# scld_winslow.net
KiCad netlist of a schematic drawn in EAGLE
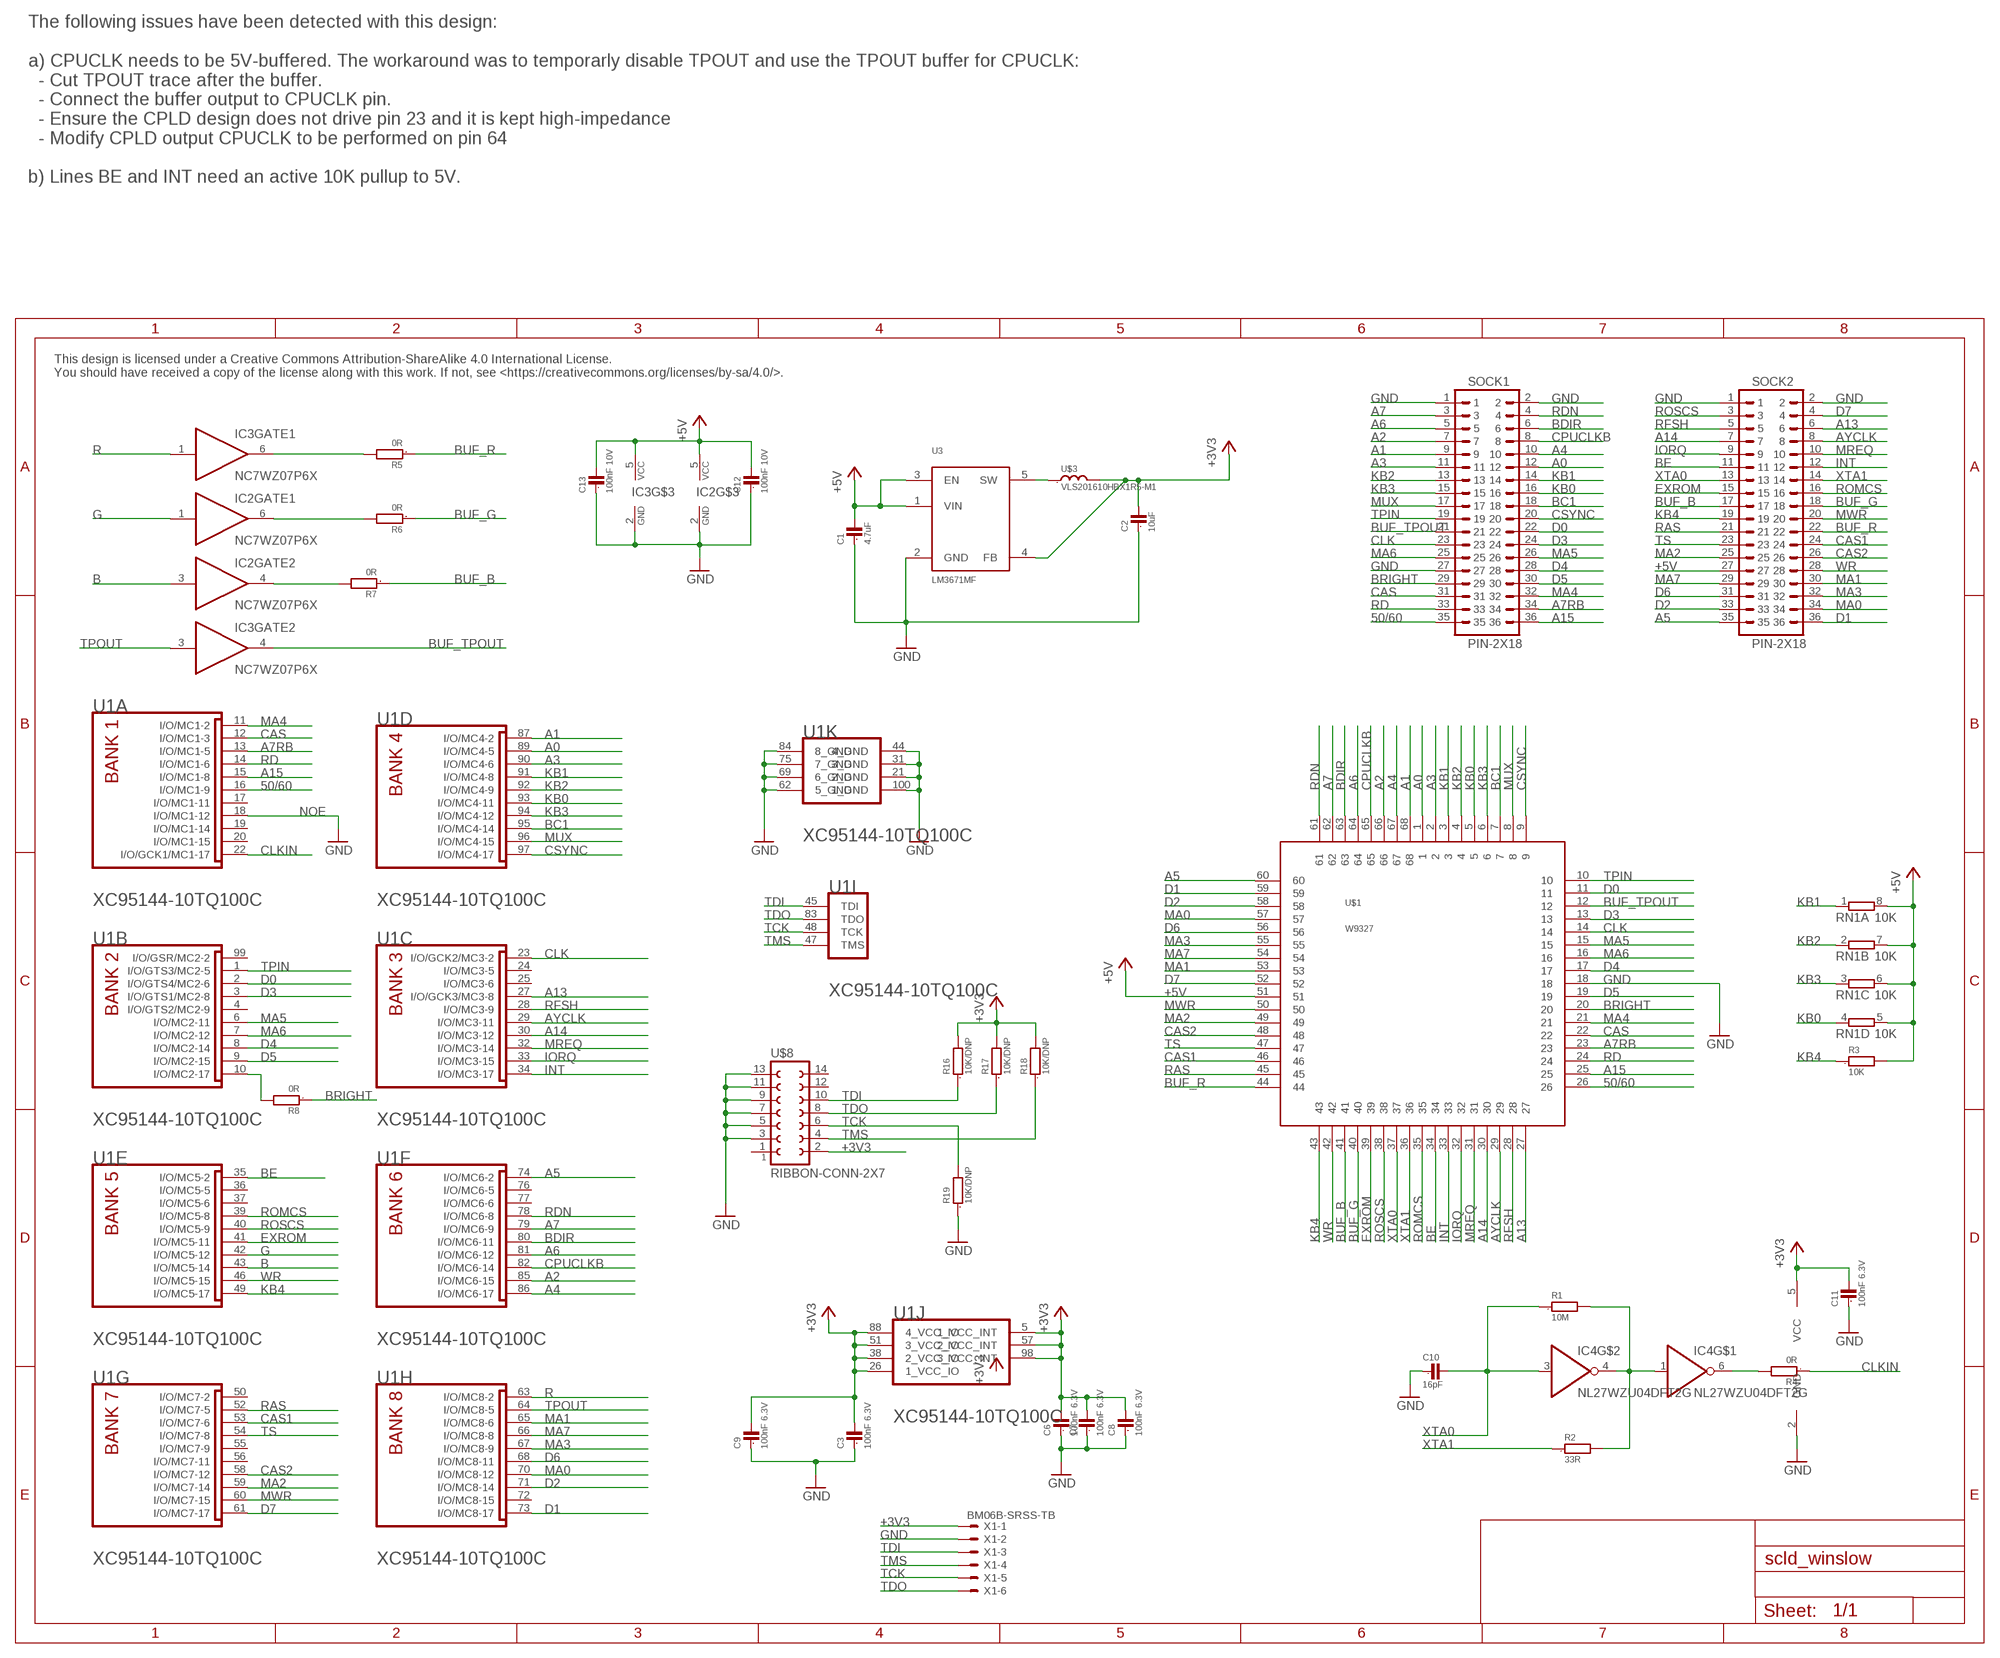
[diagram p0: schematic, sheet 1]

(export (version "E")
  (design (tool "Eeschema 10.0.6"))
  (components
    (comp (ref "C1")
      (value "4.7uF")
      (footprint "eagle-import:0805")
      (libsource (lib "eagle-import") (part "C0805"))
    )
    (comp (ref "C2")
      (value "10uF")
      (footprint "eagle-import:0805")
      (libsource (lib "eagle-import") (part "C0805"))
    )
    (comp (ref "C3")
      (value "100nF 6.3V")
      (footprint "eagle-import:0402")
      (libsource (lib "eagle-import") (part "C0402"))
    )
    (comp (ref "C6")
      (value "100nF 6.3V")
      (footprint "eagle-import:0402")
      (libsource (lib "eagle-import") (part "C0402"))
    )
    (comp (ref "C7")
      (value "100nF 6.3V")
      (footprint "eagle-import:0402")
      (libsource (lib "eagle-import") (part "C0402"))
    )
    (comp (ref "C8")
      (value "100nF 6.3V")
      (footprint "eagle-import:0402")
      (libsource (lib "eagle-import") (part "C0402"))
    )
    (comp (ref "C9")
      (value "100nF 6.3V")
      (footprint "eagle-import:0402")
      (libsource (lib "eagle-import") (part "C0402"))
    )
    (comp (ref "C10")
      (value "16pF")
      (footprint "eagle-import:0402")
      (libsource (lib "eagle-import") (part "C0402"))
    )
    (comp (ref "C11")
      (value "100nF 6.3V")
      (footprint "eagle-import:0402")
      (libsource (lib "eagle-import") (part "C0402"))
    )
    (comp (ref "C12")
      (value "100nF 10V")
      (footprint "eagle-import:0402")
      (libsource (lib "eagle-import") (part "C0402"))
    )
    (comp (ref "C13")
      (value "100nF 10V")
      (footprint "eagle-import:0402")
      (libsource (lib "eagle-import") (part "C0402"))
    )
    (comp (ref "IC2")
      (value "NC7WZ07P6X")
      (footprint "eagle-import:SC70-6")
      (libsource (lib "eagle-import") (part "NC7WZ07P6X"))
    )
    (comp (ref "IC3")
      (value "NC7WZ07P6X")
      (footprint "eagle-import:SC70-6")
      (libsource (lib "eagle-import") (part "NC7WZ07P6X"))
    )
    (comp (ref "IC4")
      (value "NL27WZU04DFT2G")
      (footprint "eagle-import:SC70-6")
      (libsource (lib "eagle-import") (part "NL27WZU04DFT2G"))
    )
    (comp (ref "R1")
      (value "10M")
      (footprint "eagle-import:0402")
      (libsource (lib "eagle-import") (part "R0402"))
    )
    (comp (ref "R2")
      (value "33R")
      (footprint "eagle-import:0402")
      (libsource (lib "eagle-import") (part "R0402"))
    )
    (comp (ref "R3")
      (value "10K")
      (footprint "eagle-import:0402")
      (libsource (lib "eagle-import") (part "R0402"))
    )
    (comp (ref "R4")
      (value "0R")
      (footprint "eagle-import:0603")
      (libsource (lib "eagle-import") (part "R0603"))
    )
    (comp (ref "R5")
      (value "0R")
      (footprint "eagle-import:0603")
      (libsource (lib "eagle-import") (part "R0603"))
    )
    (comp (ref "R6")
      (value "0R")
      (footprint "eagle-import:0603")
      (libsource (lib "eagle-import") (part "R0603"))
    )
    (comp (ref "R7")
      (value "0R")
      (footprint "eagle-import:0603")
      (libsource (lib "eagle-import") (part "R0603"))
    )
    (comp (ref "R8")
      (value "0R")
      (footprint "eagle-import:0603")
      (libsource (lib "eagle-import") (part "R0603"))
    )
    (comp (ref "R16")
      (value "10K/DNP")
      (footprint "eagle-import:0603")
      (libsource (lib "eagle-import") (part "R0603"))
    )
    (comp (ref "R17")
      (value "10K/DNP")
      (footprint "eagle-import:0603")
      (libsource (lib "eagle-import") (part "R0603"))
    )
    (comp (ref "R18")
      (value "10K/DNP")
      (footprint "eagle-import:0603")
      (libsource (lib "eagle-import") (part "R0603"))
    )
    (comp (ref "R19")
      (value "10K/DNP")
      (footprint "eagle-import:0603")
      (libsource (lib "eagle-import") (part "R0603"))
    )
    (comp (ref "RN1")
      (value "10K")
      (footprint "eagle-import:EXB28V")
      (libsource (lib "eagle-import") (part "4R-NEXB28V"))
    )
    (comp (ref "SOCK1")
      (value "PIN-2X18")
      (footprint "eagle-import:PIN-2X18")
      (libsource (lib "eagle-import") (part "PIN-2X18"))
    )
    (comp (ref "SOCK2")
      (value "PIN-2X18")
      (footprint "eagle-import:PIN-2X18")
      (libsource (lib "eagle-import") (part "PIN-2X18"))
    )
    (comp (ref "U$1")
      (value "W9327")
      (footprint "eagle-import:W9327")
      (libsource (lib "eagle-import") (part "W9327"))
    )
    (comp (ref "U$3")
      (value "VLS201610HBX1R5-M1")
      (footprint "eagle-import:IND_0806")
      (libsource (lib "eagle-import") (part "VLS201610HBX1R5-M1"))
    )
    (comp (ref "U$8")
      (value "RIBBON-CONN-2X7")
      (footprint "eagle-import:RIBBON-CONN-2X7")
      (libsource (lib "eagle-import") (part "RIBBON-CONN-2X7"))
    )
    (comp (ref "U1")
      (value "XILINX_XC95144-10TQ100CLQFP")
      (footprint "eagle-import:LQFP100")
      (libsource (lib "eagle-import") (part "XILINX_XC95144-10TQ100CLQFP"))
    )
    (comp (ref "U3")
      (value "LM3671MF")
      (footprint "eagle-import:SOT23-5L")
      (libsource (lib "eagle-import") (part "LM3671MF"))
    )
    (comp (ref "X1")
      (value "BM06B-SRSS-TB")
      (footprint "eagle-import:BM06B-SRSS-TB")
      (libsource (lib "eagle-import") (part "?M06B-SRSS-TBB"))
    )
  )
  (nets
    (net (code "1") (name "+3V3") (class "Default")
      (node (ref "C11") (pin "2") (pinfunction "2_2") (pintype "passive"))
      (node (ref "C2") (pin "2") (pinfunction "2_2") (pintype "passive"))
      (node (ref "C3") (pin "2") (pinfunction "2_2") (pintype "passive"))
      (node (ref "C6") (pin "2") (pinfunction "2_2") (pintype "passive"))
      (node (ref "C7") (pin "2") (pinfunction "2_2") (pintype "passive"))
      (node (ref "C8") (pin "2") (pinfunction "2_2") (pintype "passive"))
      (node (ref "C9") (pin "2") (pinfunction "2_2") (pintype "passive"))
      (node (ref "IC4") (pin "5") (pinfunction "VCC_5") (pintype "power_in"))
      (node (ref "R16") (pin "2") (pinfunction "2_2") (pintype "passive"))
      (node (ref "R17") (pin "2") (pinfunction "2_2") (pintype "passive"))
      (node (ref "R18") (pin "2") (pinfunction "2_2") (pintype "passive"))
      (node (ref "U$3") (pin "P$2") (pinfunction "2_P$2") (pintype "passive"))
      (node (ref "U$8") (pin "2") (pinfunction "2_2") (pintype "passive"))
      (node (ref "U1") (pin "26") (pinfunction "1_VCC_IO_26") (pintype "power_in"))
      (node (ref "U1") (pin "38") (pinfunction "2_VCC_IO_38") (pintype "power_in"))
      (node (ref "U1") (pin "5") (pinfunction "1_VCC_INT_5") (pintype "power_in"))
      (node (ref "U1") (pin "51") (pinfunction "3_VCC_IO_51") (pintype "power_in"))
      (node (ref "U1") (pin "57") (pinfunction "2_VCC_INT_57") (pintype "power_in"))
      (node (ref "U1") (pin "88") (pinfunction "4_VCC_IO_88") (pintype "power_in"))
      (node (ref "U1") (pin "98") (pinfunction "3_VCC_INT_98") (pintype "power_in"))
      (node (ref "U3") (pin "4") (pinfunction "FB_4") (pintype "passive"))
      (node (ref "X1") (pin "1") (pinfunction "S_1") (pintype "passive"))
    )
    (net (code "2") (name "+5V") (class "Default")
      (node (ref "C1") (pin "2") (pinfunction "2_2") (pintype "passive"))
      (node (ref "C12") (pin "2") (pinfunction "2_2") (pintype "passive"))
      (node (ref "C13") (pin "2") (pinfunction "2_2") (pintype "passive"))
      (node (ref "IC2") (pin "5") (pinfunction "VCC_5") (pintype "power_in"))
      (node (ref "IC3") (pin "5") (pinfunction "VCC_5") (pintype "power_in"))
      (node (ref "R3") (pin "2") (pinfunction "2_2") (pintype "passive"))
      (node (ref "RN1") (pin "5") (pinfunction "2_5") (pintype "passive"))
      (node (ref "RN1") (pin "6") (pinfunction "2_6") (pintype "passive"))
      (node (ref "RN1") (pin "7") (pinfunction "2_7") (pintype "passive"))
      (node (ref "RN1") (pin "8") (pinfunction "2_8") (pintype "passive"))
      (node (ref "SOCK2") (pin "27") (pinfunction "27_27") (pintype "passive"))
      (node (ref "U$1") (pin "51") (pinfunction "51_51") (pintype "passive"))
      (node (ref "U3") (pin "1") (pinfunction "VIN_1") (pintype "power_in"))
      (node (ref "U3") (pin "3") (pinfunction "EN_3") (pintype "input"))
    )
    (net (code "3") (name "/50{slash}60") (class "Default")
      (node (ref "SOCK1") (pin "35") (pinfunction "35_35") (pintype "passive"))
      (node (ref "U$1") (pin "26") (pinfunction "26_26") (pintype "passive"))
      (node (ref "U1") (pin "16") (pinfunction "I/O/MC1-9_16") (pintype "bidirectional"))
    )
    (net (code "4") (name "/A0") (class "Default")
      (node (ref "SOCK1") (pin "12") (pinfunction "12_12") (pintype "passive"))
      (node (ref "U$1") (pin "1") (pinfunction "1_1") (pintype "passive"))
      (node (ref "U1") (pin "89") (pinfunction "I/O/MC4-5_89") (pintype "bidirectional"))
    )
    (net (code "5") (name "/A1") (class "Default")
      (node (ref "SOCK1") (pin "9") (pinfunction "9_9") (pintype "passive"))
      (node (ref "U$1") (pin "68") (pinfunction "68_68") (pintype "passive"))
      (node (ref "U1") (pin "87") (pinfunction "I/O/MC4-2_87") (pintype "bidirectional"))
    )
    (net (code "6") (name "/A2") (class "Default")
      (node (ref "SOCK1") (pin "7") (pinfunction "7_7") (pintype "passive"))
      (node (ref "U$1") (pin "66") (pinfunction "66_66") (pintype "passive"))
      (node (ref "U1") (pin "85") (pinfunction "I/O/MC6-15_85") (pintype "bidirectional"))
    )
    (net (code "7") (name "/A3") (class "Default")
      (node (ref "SOCK1") (pin "11") (pinfunction "11_11") (pintype "passive"))
      (node (ref "U$1") (pin "2") (pinfunction "2_2") (pintype "passive"))
      (node (ref "U1") (pin "90") (pinfunction "I/O/MC4-6_90") (pintype "bidirectional"))
    )
    (net (code "8") (name "/A4") (class "Default")
      (node (ref "SOCK1") (pin "10") (pinfunction "10_10") (pintype "passive"))
      (node (ref "U$1") (pin "67") (pinfunction "67_67") (pintype "passive"))
      (node (ref "U1") (pin "86") (pinfunction "I/O/MC6-17_86") (pintype "bidirectional"))
    )
    (net (code "9") (name "/A5") (class "Default")
      (node (ref "SOCK2") (pin "35") (pinfunction "35_35") (pintype "passive"))
      (node (ref "U$1") (pin "60") (pinfunction "60_60") (pintype "passive"))
      (node (ref "U1") (pin "74") (pinfunction "I/O/MC6-2_74") (pintype "bidirectional"))
    )
    (net (code "10") (name "/A6") (class "Default")
      (node (ref "SOCK1") (pin "5") (pinfunction "5_5") (pintype "passive"))
      (node (ref "U$1") (pin "64") (pinfunction "64_64") (pintype "passive"))
      (node (ref "U1") (pin "81") (pinfunction "I/O/MC6-12_81") (pintype "bidirectional"))
    )
    (net (code "11") (name "/A7") (class "Default")
      (node (ref "SOCK1") (pin "3") (pinfunction "3_3") (pintype "passive"))
      (node (ref "U$1") (pin "62") (pinfunction "62_62") (pintype "passive"))
      (node (ref "U1") (pin "79") (pinfunction "I/O/MC6-9_79") (pintype "bidirectional"))
    )
    (net (code "12") (name "/A7RB") (class "Default")
      (node (ref "SOCK1") (pin "34") (pinfunction "34_34") (pintype "passive"))
      (node (ref "U$1") (pin "23") (pinfunction "23_23") (pintype "passive"))
      (node (ref "U1") (pin "13") (pinfunction "I/O/MC1-5_13") (pintype "bidirectional"))
    )
    (net (code "13") (name "/A13") (class "Default")
      (node (ref "SOCK2") (pin "6") (pinfunction "6_6") (pintype "passive"))
      (node (ref "U$1") (pin "27") (pinfunction "27_27") (pintype "passive"))
      (node (ref "U1") (pin "27") (pinfunction "I/O/GCK3/MC3-8_27") (pintype "bidirectional"))
    )
    (net (code "14") (name "/A14") (class "Default")
      (node (ref "SOCK2") (pin "7") (pinfunction "7_7") (pintype "passive"))
      (node (ref "U$1") (pin "30") (pinfunction "30_30") (pintype "passive"))
      (node (ref "U1") (pin "30") (pinfunction "I/O/MC3-12_30") (pintype "bidirectional"))
    )
    (net (code "15") (name "/A15") (class "Default")
      (node (ref "SOCK1") (pin "36") (pinfunction "36_36") (pintype "passive"))
      (node (ref "U$1") (pin "25") (pinfunction "25_25") (pintype "passive"))
      (node (ref "U1") (pin "15") (pinfunction "I/O/MC1-8_15") (pintype "bidirectional"))
    )
    (net (code "16") (name "/AYCLK") (class "Default")
      (node (ref "SOCK2") (pin "8") (pinfunction "8_8") (pintype "passive"))
      (node (ref "U$1") (pin "29") (pinfunction "29_29") (pintype "passive"))
      (node (ref "U1") (pin "29") (pinfunction "I/O/MC3-11_29") (pintype "bidirectional"))
    )
    (net (code "17") (name "/B") (class "Default")
      (node (ref "IC2") (pin "3") (pinfunction "I_3") (pintype "input"))
      (node (ref "U1") (pin "43") (pinfunction "I/O/MC5-14_43") (pintype "bidirectional"))
    )
    (net (code "18") (name "/BC1") (class "Default")
      (node (ref "SOCK1") (pin "18") (pinfunction "18_18") (pintype "passive"))
      (node (ref "U$1") (pin "7") (pinfunction "7_7") (pintype "passive"))
      (node (ref "U1") (pin "95") (pinfunction "I/O/MC4-14_95") (pintype "bidirectional"))
    )
    (net (code "19") (name "/BDIR") (class "Default")
      (node (ref "SOCK1") (pin "6") (pinfunction "6_6") (pintype "passive"))
      (node (ref "U$1") (pin "63") (pinfunction "63_63") (pintype "passive"))
      (node (ref "U1") (pin "80") (pinfunction "I/O/MC6-11_80") (pintype "bidirectional"))
    )
    (net (code "20") (name "/BE") (class "Default")
      (node (ref "SOCK2") (pin "11") (pinfunction "11_11") (pintype "passive"))
      (node (ref "U$1") (pin "34") (pinfunction "34_34") (pintype "passive"))
      (node (ref "U1") (pin "35") (pinfunction "I/O/MC5-2_35") (pintype "bidirectional"))
    )
    (net (code "21") (name "/BRIGHT") (class "Default")
      (node (ref "R8") (pin "1") (pinfunction "1_1") (pintype "passive"))
      (node (ref "SOCK1") (pin "29") (pinfunction "29_29") (pintype "passive"))
      (node (ref "U$1") (pin "20") (pinfunction "20_20") (pintype "passive"))
    )
    (net (code "22") (name "/BUF_B") (class "Default")
      (node (ref "R7") (pin "1") (pinfunction "1_1") (pintype "passive"))
      (node (ref "SOCK2") (pin "17") (pinfunction "17_17") (pintype "passive"))
      (node (ref "U$1") (pin "41") (pinfunction "41_41") (pintype "passive"))
    )
    (net (code "23") (name "/BUF_G") (class "Default")
      (node (ref "R6") (pin "1") (pinfunction "1_1") (pintype "passive"))
      (node (ref "SOCK2") (pin "18") (pinfunction "18_18") (pintype "passive"))
      (node (ref "U$1") (pin "40") (pinfunction "40_40") (pintype "passive"))
    )
    (net (code "24") (name "/BUF_R") (class "Default")
      (node (ref "R5") (pin "1") (pinfunction "1_1") (pintype "passive"))
      (node (ref "SOCK2") (pin "22") (pinfunction "22_22") (pintype "passive"))
      (node (ref "U$1") (pin "44") (pinfunction "44_44") (pintype "passive"))
    )
    (net (code "25") (name "/BUF_TPOUT") (class "Default")
      (node (ref "IC3") (pin "4") (pinfunction "O_4") (pintype "tri_state"))
      (node (ref "SOCK1") (pin "21") (pinfunction "21_21") (pintype "passive"))
      (node (ref "U$1") (pin "12") (pinfunction "12_12") (pintype "passive"))
    )
    (net (code "26") (name "/CAS") (class "Default")
      (node (ref "SOCK1") (pin "31") (pinfunction "31_31") (pintype "passive"))
      (node (ref "U$1") (pin "22") (pinfunction "22_22") (pintype "passive"))
      (node (ref "U1") (pin "12") (pinfunction "I/O/MC1-3_12") (pintype "bidirectional"))
    )
    (net (code "27") (name "/CAS1") (class "Default")
      (node (ref "SOCK2") (pin "24") (pinfunction "24_24") (pintype "passive"))
      (node (ref "U$1") (pin "46") (pinfunction "46_46") (pintype "passive"))
      (node (ref "U1") (pin "53") (pinfunction "I/O/MC7-6_53") (pintype "bidirectional"))
    )
    (net (code "28") (name "/CAS2") (class "Default")
      (node (ref "SOCK2") (pin "26") (pinfunction "26_26") (pintype "passive"))
      (node (ref "U$1") (pin "48") (pinfunction "48_48") (pintype "passive"))
      (node (ref "U1") (pin "58") (pinfunction "I/O/MC7-12_58") (pintype "bidirectional"))
    )
    (net (code "29") (name "/CLK") (class "Default")
      (node (ref "SOCK1") (pin "23") (pinfunction "23_23") (pintype "passive"))
      (node (ref "U$1") (pin "14") (pinfunction "14_14") (pintype "passive"))
      (node (ref "U1") (pin "23") (pinfunction "I/O/GCK2/MC3-2_23") (pintype "bidirectional"))
    )
    (net (code "30") (name "/CLKIN") (class "Default")
      (node (ref "R4") (pin "1") (pinfunction "1_1") (pintype "passive"))
      (node (ref "U1") (pin "22") (pinfunction "I/O/GCK1/MC1-17_22") (pintype "bidirectional"))
    )
    (net (code "31") (name "/CPUCLKB") (class "Default")
      (node (ref "SOCK1") (pin "8") (pinfunction "8_8") (pintype "passive"))
      (node (ref "U$1") (pin "65") (pinfunction "65_65") (pintype "passive"))
      (node (ref "U1") (pin "82") (pinfunction "I/O/MC6-14_82") (pintype "bidirectional"))
    )
    (net (code "32") (name "/CSYNC") (class "Default")
      (node (ref "SOCK1") (pin "20") (pinfunction "20_20") (pintype "passive"))
      (node (ref "U$1") (pin "9") (pinfunction "9_9") (pintype "passive"))
      (node (ref "U1") (pin "97") (pinfunction "I/O/MC4-17_97") (pintype "bidirectional"))
    )
    (net (code "33") (name "/D0") (class "Default")
      (node (ref "SOCK1") (pin "22") (pinfunction "22_22") (pintype "passive"))
      (node (ref "U$1") (pin "11") (pinfunction "11_11") (pintype "passive"))
      (node (ref "U1") (pin "2") (pinfunction "I/O/GTS4/MC2-6_2") (pintype "bidirectional"))
    )
    (net (code "34") (name "/D1") (class "Default")
      (node (ref "SOCK2") (pin "36") (pinfunction "36_36") (pintype "passive"))
      (node (ref "U$1") (pin "59") (pinfunction "59_59") (pintype "passive"))
      (node (ref "U1") (pin "73") (pinfunction "I/O/MC8-17_73") (pintype "bidirectional"))
    )
    (net (code "35") (name "/D2") (class "Default")
      (node (ref "SOCK2") (pin "33") (pinfunction "33_33") (pintype "passive"))
      (node (ref "U$1") (pin "58") (pinfunction "58_58") (pintype "passive"))
      (node (ref "U1") (pin "71") (pinfunction "I/O/MC8-14_71") (pintype "bidirectional"))
    )
    (net (code "36") (name "/D3") (class "Default")
      (node (ref "SOCK1") (pin "24") (pinfunction "24_24") (pintype "passive"))
      (node (ref "U$1") (pin "13") (pinfunction "13_13") (pintype "passive"))
      (node (ref "U1") (pin "3") (pinfunction "I/O/GTS1/MC2-8_3") (pintype "bidirectional"))
    )
    (net (code "37") (name "/D4") (class "Default")
      (node (ref "SOCK1") (pin "28") (pinfunction "28_28") (pintype "passive"))
      (node (ref "U$1") (pin "17") (pinfunction "17_17") (pintype "passive"))
      (node (ref "U1") (pin "8") (pinfunction "I/O/MC2-14_8") (pintype "bidirectional"))
    )
    (net (code "38") (name "/D5") (class "Default")
      (node (ref "SOCK1") (pin "30") (pinfunction "30_30") (pintype "passive"))
      (node (ref "U$1") (pin "19") (pinfunction "19_19") (pintype "passive"))
      (node (ref "U1") (pin "9") (pinfunction "I/O/MC2-15_9") (pintype "bidirectional"))
    )
    (net (code "39") (name "/D6") (class "Default")
      (node (ref "SOCK2") (pin "31") (pinfunction "31_31") (pintype "passive"))
      (node (ref "U$1") (pin "56") (pinfunction "56_56") (pintype "passive"))
      (node (ref "U1") (pin "68") (pinfunction "I/O/MC8-11_68") (pintype "bidirectional"))
    )
    (net (code "40") (name "/D7") (class "Default")
      (node (ref "SOCK2") (pin "4") (pinfunction "4_4") (pintype "passive"))
      (node (ref "U$1") (pin "52") (pinfunction "52_52") (pintype "passive"))
      (node (ref "U1") (pin "61") (pinfunction "I/O/MC7-17_61") (pintype "bidirectional"))
    )
    (net (code "41") (name "/EXROM") (class "Default")
      (node (ref "SOCK2") (pin "15") (pinfunction "15_15") (pintype "passive"))
      (node (ref "U$1") (pin "39") (pinfunction "39_39") (pintype "passive"))
      (node (ref "U1") (pin "41") (pinfunction "I/O/MC5-11_41") (pintype "bidirectional"))
    )
    (net (code "42") (name "/G") (class "Default")
      (node (ref "IC2") (pin "1") (pinfunction "I_1") (pintype "input"))
      (node (ref "U1") (pin "42") (pinfunction "I/O/MC5-12_42") (pintype "bidirectional"))
    )
    (net (code "43") (name "/INT") (class "Default")
      (node (ref "SOCK2") (pin "12") (pinfunction "12_12") (pintype "passive"))
      (node (ref "U$1") (pin "33") (pinfunction "33_33") (pintype "passive"))
      (node (ref "U1") (pin "34") (pinfunction "I/O/MC3-17_34") (pintype "bidirectional"))
    )
    (net (code "44") (name "/IORQ") (class "Default")
      (node (ref "SOCK2") (pin "9") (pinfunction "9_9") (pintype "passive"))
      (node (ref "U$1") (pin "32") (pinfunction "32_32") (pintype "passive"))
      (node (ref "U1") (pin "33") (pinfunction "I/O/MC3-15_33") (pintype "bidirectional"))
    )
    (net (code "45") (name "/KB0") (class "Default")
      (node (ref "RN1") (pin "4") (pinfunction "1_4") (pintype "passive"))
      (node (ref "SOCK1") (pin "16") (pinfunction "16_16") (pintype "passive"))
      (node (ref "U$1") (pin "5") (pinfunction "5_5") (pintype "passive"))
      (node (ref "U1") (pin "93") (pinfunction "I/O/MC4-11_93") (pintype "bidirectional"))
    )
    (net (code "46") (name "/KB1") (class "Default")
      (node (ref "RN1") (pin "1") (pinfunction "1_1") (pintype "passive"))
      (node (ref "SOCK1") (pin "14") (pinfunction "14_14") (pintype "passive"))
      (node (ref "U$1") (pin "3") (pinfunction "3_3") (pintype "passive"))
      (node (ref "U1") (pin "91") (pinfunction "I/O/MC4-8_91") (pintype "bidirectional"))
    )
    (net (code "47") (name "/KB2") (class "Default")
      (node (ref "RN1") (pin "2") (pinfunction "1_2") (pintype "passive"))
      (node (ref "SOCK1") (pin "13") (pinfunction "13_13") (pintype "passive"))
      (node (ref "U$1") (pin "4") (pinfunction "4_4") (pintype "passive"))
      (node (ref "U1") (pin "92") (pinfunction "I/O/MC4-9_92") (pintype "bidirectional"))
    )
    (net (code "48") (name "/KB3") (class "Default")
      (node (ref "RN1") (pin "3") (pinfunction "1_3") (pintype "passive"))
      (node (ref "SOCK1") (pin "15") (pinfunction "15_15") (pintype "passive"))
      (node (ref "U$1") (pin "6") (pinfunction "6_6") (pintype "passive"))
      (node (ref "U1") (pin "94") (pinfunction "I/O/MC4-12_94") (pintype "bidirectional"))
    )
    (net (code "49") (name "/KB4") (class "Default")
      (node (ref "R3") (pin "1") (pinfunction "1_1") (pintype "passive"))
      (node (ref "SOCK2") (pin "19") (pinfunction "19_19") (pintype "passive"))
      (node (ref "U$1") (pin "43") (pinfunction "43_43") (pintype "passive"))
      (node (ref "U1") (pin "49") (pinfunction "I/O/MC5-17_49") (pintype "bidirectional"))
    )
    (net (code "50") (name "/MA0") (class "Default")
      (node (ref "SOCK2") (pin "34") (pinfunction "34_34") (pintype "passive"))
      (node (ref "U$1") (pin "57") (pinfunction "57_57") (pintype "passive"))
      (node (ref "U1") (pin "70") (pinfunction "I/O/MC8-12_70") (pintype "bidirectional"))
    )
    (net (code "51") (name "/MA1") (class "Default")
      (node (ref "SOCK2") (pin "30") (pinfunction "30_30") (pintype "passive"))
      (node (ref "U$1") (pin "53") (pinfunction "53_53") (pintype "passive"))
      (node (ref "U1") (pin "65") (pinfunction "I/O/MC8-6_65") (pintype "bidirectional"))
    )
    (net (code "52") (name "/MA2") (class "Default")
      (node (ref "SOCK2") (pin "25") (pinfunction "25_25") (pintype "passive"))
      (node (ref "U$1") (pin "49") (pinfunction "49_49") (pintype "passive"))
      (node (ref "U1") (pin "59") (pinfunction "I/O/MC7-14_59") (pintype "bidirectional"))
    )
    (net (code "53") (name "/MA3") (class "Default")
      (node (ref "SOCK2") (pin "32") (pinfunction "32_32") (pintype "passive"))
      (node (ref "U$1") (pin "55") (pinfunction "55_55") (pintype "passive"))
      (node (ref "U1") (pin "67") (pinfunction "I/O/MC8-9_67") (pintype "bidirectional"))
    )
    (net (code "54") (name "/MA4") (class "Default")
      (node (ref "SOCK1") (pin "32") (pinfunction "32_32") (pintype "passive"))
      (node (ref "U$1") (pin "21") (pinfunction "21_21") (pintype "passive"))
      (node (ref "U1") (pin "11") (pinfunction "I/O/MC1-2_11") (pintype "bidirectional"))
    )
    (net (code "55") (name "/MA5") (class "Default")
      (node (ref "SOCK1") (pin "26") (pinfunction "26_26") (pintype "passive"))
      (node (ref "U$1") (pin "15") (pinfunction "15_15") (pintype "passive"))
      (node (ref "U1") (pin "6") (pinfunction "I/O/MC2-11_6") (pintype "bidirectional"))
    )
    (net (code "56") (name "/MA6") (class "Default")
      (node (ref "SOCK1") (pin "25") (pinfunction "25_25") (pintype "passive"))
      (node (ref "U$1") (pin "16") (pinfunction "16_16") (pintype "passive"))
      (node (ref "U1") (pin "7") (pinfunction "I/O/MC2-12_7") (pintype "bidirectional"))
    )
    (net (code "57") (name "/MA7") (class "Default")
      (node (ref "SOCK2") (pin "29") (pinfunction "29_29") (pintype "passive"))
      (node (ref "U$1") (pin "54") (pinfunction "54_54") (pintype "passive"))
      (node (ref "U1") (pin "66") (pinfunction "I/O/MC8-8_66") (pintype "bidirectional"))
    )
    (net (code "58") (name "/MREQ") (class "Default")
      (node (ref "SOCK2") (pin "10") (pinfunction "10_10") (pintype "passive"))
      (node (ref "U$1") (pin "31") (pinfunction "31_31") (pintype "passive"))
      (node (ref "U1") (pin "32") (pinfunction "I/O/MC3-14_32") (pintype "bidirectional"))
    )
    (net (code "59") (name "/MUX") (class "Default")
      (node (ref "SOCK1") (pin "17") (pinfunction "17_17") (pintype "passive"))
      (node (ref "U$1") (pin "8") (pinfunction "8_8") (pintype "passive"))
      (node (ref "U1") (pin "96") (pinfunction "I/O/MC4-15_96") (pintype "bidirectional"))
    )
    (net (code "60") (name "/MWR") (class "Default")
      (node (ref "SOCK2") (pin "20") (pinfunction "20_20") (pintype "passive"))
      (node (ref "U$1") (pin "50") (pinfunction "50_50") (pintype "passive"))
      (node (ref "U1") (pin "60") (pinfunction "I/O/MC7-15_60") (pintype "bidirectional"))
    )
    (net (code "61") (name "/R") (class "Default")
      (node (ref "IC3") (pin "1") (pinfunction "I_1") (pintype "input"))
      (node (ref "U1") (pin "63") (pinfunction "I/O/MC8-2_63") (pintype "bidirectional"))
    )
    (net (code "62") (name "/RAS") (class "Default")
      (node (ref "SOCK2") (pin "21") (pinfunction "21_21") (pintype "passive"))
      (node (ref "U$1") (pin "45") (pinfunction "45_45") (pintype "passive"))
      (node (ref "U1") (pin "52") (pinfunction "I/O/MC7-5_52") (pintype "bidirectional"))
    )
    (net (code "63") (name "/RD") (class "Default")
      (node (ref "SOCK1") (pin "33") (pinfunction "33_33") (pintype "passive"))
      (node (ref "U$1") (pin "24") (pinfunction "24_24") (pintype "passive"))
      (node (ref "U1") (pin "14") (pinfunction "I/O/MC1-6_14") (pintype "bidirectional"))
    )
    (net (code "64") (name "/RDN") (class "Default")
      (node (ref "SOCK1") (pin "4") (pinfunction "4_4") (pintype "passive"))
      (node (ref "U$1") (pin "61") (pinfunction "61_61") (pintype "passive"))
      (node (ref "U1") (pin "78") (pinfunction "I/O/MC6-8_78") (pintype "bidirectional"))
    )
    (net (code "65") (name "/RFSH") (class "Default")
      (node (ref "SOCK2") (pin "5") (pinfunction "5_5") (pintype "passive"))
      (node (ref "U$1") (pin "28") (pinfunction "28_28") (pintype "passive"))
      (node (ref "U1") (pin "28") (pinfunction "I/O/MC3-9_28") (pintype "bidirectional"))
    )
    (net (code "66") (name "/ROMCS") (class "Default")
      (node (ref "SOCK2") (pin "16") (pinfunction "16_16") (pintype "passive"))
      (node (ref "U$1") (pin "35") (pinfunction "35_35") (pintype "passive"))
      (node (ref "U1") (pin "39") (pinfunction "I/O/MC5-8_39") (pintype "bidirectional"))
    )
    (net (code "67") (name "/ROSCS") (class "Default")
      (node (ref "SOCK2") (pin "3") (pinfunction "3_3") (pintype "passive"))
      (node (ref "U$1") (pin "38") (pinfunction "38_38") (pintype "passive"))
      (node (ref "U1") (pin "40") (pinfunction "I/O/MC5-9_40") (pintype "bidirectional"))
    )
    (net (code "68") (name "/TCK") (class "Default")
      (node (ref "R19") (pin "2") (pinfunction "2_2") (pintype "passive"))
      (node (ref "U$8") (pin "6") (pinfunction "6_6") (pintype "passive"))
      (node (ref "U1") (pin "48") (pinfunction "TCK_48") (pintype "input"))
      (node (ref "X1") (pin "5") (pinfunction "S_5") (pintype "passive"))
    )
    (net (code "69") (name "/TDI") (class "Default")
      (node (ref "R16") (pin "1") (pinfunction "1_1") (pintype "passive"))
      (node (ref "U$8") (pin "10") (pinfunction "10_10") (pintype "passive"))
      (node (ref "U1") (pin "45") (pinfunction "TDI_45") (pintype "input"))
      (node (ref "X1") (pin "3") (pinfunction "S_3") (pintype "passive"))
    )
    (net (code "70") (name "/TDO") (class "Default")
      (node (ref "R17") (pin "1") (pinfunction "1_1") (pintype "passive"))
      (node (ref "U$8") (pin "8") (pinfunction "8_8") (pintype "passive"))
      (node (ref "U1") (pin "83") (pinfunction "TDO_83") (pintype "output"))
      (node (ref "X1") (pin "6") (pinfunction "S_6") (pintype "passive"))
    )
    (net (code "71") (name "/TMS") (class "Default")
      (node (ref "R18") (pin "1") (pinfunction "1_1") (pintype "passive"))
      (node (ref "U$8") (pin "4") (pinfunction "4_4") (pintype "passive"))
      (node (ref "U1") (pin "47") (pinfunction "TMS_47") (pintype "input"))
      (node (ref "X1") (pin "4") (pinfunction "S_4") (pintype "passive"))
    )
    (net (code "72") (name "/TPIN") (class "Default")
      (node (ref "SOCK1") (pin "19") (pinfunction "19_19") (pintype "passive"))
      (node (ref "U$1") (pin "10") (pinfunction "10_10") (pintype "passive"))
      (node (ref "U1") (pin "1") (pinfunction "I/O/GTS3/MC2-5_1") (pintype "bidirectional"))
    )
    (net (code "73") (name "/TPOUT") (class "Default")
      (node (ref "IC3") (pin "3") (pinfunction "I_3") (pintype "input"))
      (node (ref "U1") (pin "64") (pinfunction "I/O/MC8-5_64") (pintype "bidirectional"))
    )
    (net (code "74") (name "/TS") (class "Default")
      (node (ref "SOCK2") (pin "23") (pinfunction "23_23") (pintype "passive"))
      (node (ref "U$1") (pin "47") (pinfunction "47_47") (pintype "passive"))
      (node (ref "U1") (pin "54") (pinfunction "I/O/MC7-8_54") (pintype "bidirectional"))
    )
    (net (code "75") (name "/WR") (class "Default")
      (node (ref "SOCK2") (pin "28") (pinfunction "28_28") (pintype "passive"))
      (node (ref "U$1") (pin "42") (pinfunction "42_42") (pintype "passive"))
      (node (ref "U1") (pin "46") (pinfunction "I/O/MC5-15_46") (pintype "bidirectional"))
    )
    (net (code "76") (name "/XTA0") (class "Default")
      (node (ref "C10") (pin "2") (pinfunction "2_2") (pintype "passive"))
      (node (ref "IC4") (pin "3") (pinfunction "I_3") (pintype "input"))
      (node (ref "R1") (pin "1") (pinfunction "1_1") (pintype "passive"))
      (node (ref "SOCK2") (pin "13") (pinfunction "13_13") (pintype "passive"))
      (node (ref "U$1") (pin "37") (pinfunction "37_37") (pintype "passive"))
    )
    (net (code "77") (name "/XTA1") (class "Default")
      (node (ref "R2") (pin "1") (pinfunction "1_1") (pintype "passive"))
      (node (ref "SOCK2") (pin "14") (pinfunction "14_14") (pintype "passive"))
      (node (ref "U$1") (pin "36") (pinfunction "36_36") (pintype "passive"))
    )
    (net (code "78") (name "GND") (class "Default")
      (node (ref "C1") (pin "1") (pinfunction "1_1") (pintype "passive"))
      (node (ref "C10") (pin "1") (pinfunction "1_1") (pintype "passive"))
      (node (ref "C11") (pin "1") (pinfunction "1_1") (pintype "passive"))
      (node (ref "C12") (pin "1") (pinfunction "1_1") (pintype "passive"))
      (node (ref "C13") (pin "1") (pinfunction "1_1") (pintype "passive"))
      (node (ref "C2") (pin "1") (pinfunction "1_1") (pintype "passive"))
      (node (ref "C3") (pin "1") (pinfunction "1_1") (pintype "passive"))
      (node (ref "C6") (pin "1") (pinfunction "1_1") (pintype "passive"))
      (node (ref "C7") (pin "1") (pinfunction "1_1") (pintype "passive"))
      (node (ref "C8") (pin "1") (pinfunction "1_1") (pintype "passive"))
      (node (ref "C9") (pin "1") (pinfunction "1_1") (pintype "passive"))
      (node (ref "IC2") (pin "2") (pinfunction "GND_2") (pintype "power_in"))
      (node (ref "IC3") (pin "2") (pinfunction "GND_2") (pintype "power_in"))
      (node (ref "IC4") (pin "2") (pinfunction "GND_2") (pintype "power_in"))
      (node (ref "R19") (pin "1") (pinfunction "1_1") (pintype "passive"))
      (node (ref "SOCK1") (pin "1") (pinfunction "1_1") (pintype "passive"))
      (node (ref "SOCK1") (pin "2") (pinfunction "2_2") (pintype "passive"))
      (node (ref "SOCK1") (pin "27") (pinfunction "27_27") (pintype "passive"))
      (node (ref "SOCK2") (pin "1") (pinfunction "1_1") (pintype "passive"))
      (node (ref "SOCK2") (pin "2") (pinfunction "2_2") (pintype "passive"))
      (node (ref "U$1") (pin "18") (pinfunction "18_18") (pintype "passive"))
      (node (ref "U$8") (pin "11") (pinfunction "11_11") (pintype "passive"))
      (node (ref "U$8") (pin "13") (pinfunction "13_13") (pintype "passive"))
      (node (ref "U$8") (pin "3") (pinfunction "3_3") (pintype "passive"))
      (node (ref "U$8") (pin "5") (pinfunction "5_5") (pintype "passive"))
      (node (ref "U$8") (pin "7") (pinfunction "7_7") (pintype "passive"))
      (node (ref "U$8") (pin "9") (pinfunction "9_9") (pintype "passive"))
      (node (ref "U1") (pin "100") (pinfunction "1_GND_100") (pintype "power_in"))
      (node (ref "U1") (pin "18") (pinfunction "I/O/MC1-12_18") (pintype "bidirectional"))
      (node (ref "U1") (pin "21") (pinfunction "2_GND_21") (pintype "power_in"))
      (node (ref "U1") (pin "31") (pinfunction "3_GND_31") (pintype "power_in"))
      (node (ref "U1") (pin "44") (pinfunction "4_GND_44") (pintype "power_in"))
      (node (ref "U1") (pin "62") (pinfunction "5_GND_62") (pintype "power_in"))
      (node (ref "U1") (pin "69") (pinfunction "6_GND_69") (pintype "power_in"))
      (node (ref "U1") (pin "75") (pinfunction "7_GND_75") (pintype "power_in"))
      (node (ref "U1") (pin "84") (pinfunction "8_GND_84") (pintype "power_in"))
      (node (ref "U3") (pin "2") (pinfunction "GND_2") (pintype "power_in"))
      (node (ref "X1") (pin "2") (pinfunction "S_2") (pintype "passive"))
    )
    (net (code "79") (name "Net-(IC2B-O)") (class "Default")
      (node (ref "IC2") (pin "6") (pinfunction "O_6") (pintype "tri_state"))
      (node (ref "R6") (pin "2") (pinfunction "2_2") (pintype "passive"))
    )
    (net (code "80") (name "Net-(IC2C-O)") (class "Default")
      (node (ref "IC2") (pin "4") (pinfunction "O_4") (pintype "tri_state"))
      (node (ref "R7") (pin "2") (pinfunction "2_2") (pintype "passive"))
    )
    (net (code "81") (name "Net-(IC3B-O)") (class "Default")
      (node (ref "IC3") (pin "6") (pinfunction "O_6") (pintype "tri_state"))
      (node (ref "R5") (pin "2") (pinfunction "2_2") (pintype "passive"))
    )
    (net (code "82") (name "Net-(IC4A-I)") (class "Default")
      (node (ref "IC4") (pin "1") (pinfunction "I_1") (pintype "input"))
      (node (ref "IC4") (pin "4") (pinfunction "O_4") (pintype "output"))
      (node (ref "R1") (pin "2") (pinfunction "2_2") (pintype "passive"))
      (node (ref "R2") (pin "2") (pinfunction "2_2") (pintype "passive"))
    )
    (net (code "83") (name "Net-(IC4A-O)") (class "Default")
      (node (ref "IC4") (pin "6") (pinfunction "O_6") (pintype "output"))
      (node (ref "R4") (pin "2") (pinfunction "2_2") (pintype "passive"))
    )
    (net (code "84") (name "Net-(U$3-1)") (class "Default")
      (node (ref "U$3") (pin "P$1") (pinfunction "1_P$1") (pintype "passive"))
      (node (ref "U3") (pin "5") (pinfunction "SW_5") (pintype "passive"))
    )
    (net (code "85") (name "Net-(U1B-I{slash}O{slash}MC2-17)") (class "Default")
      (node (ref "R8") (pin "2") (pinfunction "2_2") (pintype "passive"))
      (node (ref "U1") (pin "10") (pinfunction "I/O/MC2-17_10") (pintype "bidirectional"))
    )
    (net (code "86") (name "unconnected-(U$8-Pad1)") (class "Default")
      (node (ref "U$8") (pin "1") (pinfunction "1_1") (pintype "passive"))
    )
    (net (code "87") (name "unconnected-(U$8-Pad12)") (class "Default")
      (node (ref "U$8") (pin "12") (pinfunction "12_12") (pintype "passive"))
    )
    (net (code "88") (name "unconnected-(U$8-Pad14)") (class "Default")
      (node (ref "U$8") (pin "14") (pinfunction "14_14") (pintype "passive"))
    )
    (net (code "89") (name "unconnected-(U1A-I{slash}O{slash}MC1-11-Pad17)") (class "Default")
      (node (ref "U1") (pin "17") (pinfunction "I/O/MC1-11_17") (pintype "bidirectional"))
    )
    (net (code "90") (name "unconnected-(U1A-I{slash}O{slash}MC1-14-Pad19)") (class "Default")
      (node (ref "U1") (pin "19") (pinfunction "I/O/MC1-14_19") (pintype "bidirectional"))
    )
    (net (code "91") (name "unconnected-(U1A-I{slash}O{slash}MC1-15-Pad20)") (class "Default")
      (node (ref "U1") (pin "20") (pinfunction "I/O/MC1-15_20") (pintype "bidirectional"))
    )
    (net (code "92") (name "unconnected-(U1B-I{slash}O{slash}GSR{slash}MC2-2-Pad99)") (class "Default")
      (node (ref "U1") (pin "99") (pinfunction "I/O/GSR/MC2-2_99") (pintype "bidirectional"))
    )
    (net (code "93") (name "unconnected-(U1B-I{slash}O{slash}GTS2{slash}MC2-9-Pad4)") (class "Default")
      (node (ref "U1") (pin "4") (pinfunction "I/O/GTS2/MC2-9_4") (pintype "bidirectional"))
    )
    (net (code "94") (name "unconnected-(U1C-I{slash}O{slash}MC3-5-Pad24)") (class "Default")
      (node (ref "U1") (pin "24") (pinfunction "I/O/MC3-5_24") (pintype "bidirectional"))
    )
    (net (code "95") (name "unconnected-(U1C-I{slash}O{slash}MC3-6-Pad25)") (class "Default")
      (node (ref "U1") (pin "25") (pinfunction "I/O/MC3-6_25") (pintype "bidirectional"))
    )
    (net (code "96") (name "unconnected-(U1E-I{slash}O{slash}MC5-5-Pad36)") (class "Default")
      (node (ref "U1") (pin "36") (pinfunction "I/O/MC5-5_36") (pintype "bidirectional"))
    )
    (net (code "97") (name "unconnected-(U1E-I{slash}O{slash}MC5-6-Pad37)") (class "Default")
      (node (ref "U1") (pin "37") (pinfunction "I/O/MC5-6_37") (pintype "bidirectional"))
    )
    (net (code "98") (name "unconnected-(U1F-I{slash}O{slash}MC6-5-Pad76)") (class "Default")
      (node (ref "U1") (pin "76") (pinfunction "I/O/MC6-5_76") (pintype "bidirectional"))
    )
    (net (code "99") (name "unconnected-(U1F-I{slash}O{slash}MC6-6-Pad77)") (class "Default")
      (node (ref "U1") (pin "77") (pinfunction "I/O/MC6-6_77") (pintype "bidirectional"))
    )
    (net (code "100") (name "unconnected-(U1G-I{slash}O{slash}MC7-2-Pad50)") (class "Default")
      (node (ref "U1") (pin "50") (pinfunction "I/O/MC7-2_50") (pintype "bidirectional"))
    )
    (net (code "101") (name "unconnected-(U1G-I{slash}O{slash}MC7-9-Pad55)") (class "Default")
      (node (ref "U1") (pin "55") (pinfunction "I/O/MC7-9_55") (pintype "bidirectional"))
    )
    (net (code "102") (name "unconnected-(U1G-I{slash}O{slash}MC7-11-Pad56)") (class "Default")
      (node (ref "U1") (pin "56") (pinfunction "I/O/MC7-11_56") (pintype "bidirectional"))
    )
    (net (code "103") (name "unconnected-(U1H-I{slash}O{slash}MC8-15-Pad72)") (class "Default")
      (node (ref "U1") (pin "72") (pinfunction "I/O/MC8-15_72") (pintype "bidirectional"))
    )
  )
)
